# Cas_1.net
KiCad netlist of a schematic drawn in Altium Designer
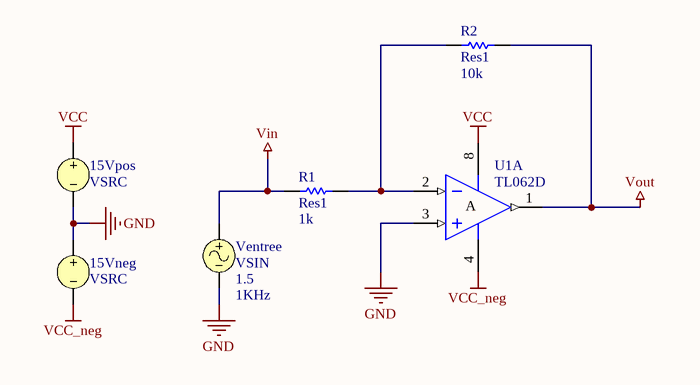
[diagram p0: Cas_1.SchDoc]

(export (version "E")
  (design (tool "Eeschema 10.0.6"))
  (components
    (comp (ref "15Vneg")
      (value "VSRC")
      (description "Voltage Source")
      (fields (field (name "PUBLISHER") "Altium Limited"))
      (libsource (lib "Simulation Generic Components") (part "VSRC"))
    )
    (comp (ref "15Vpos")
      (value "VSRC")
      (description "Voltage Source")
      (fields (field (name "PUBLISHER") "Altium Limited"))
      (libsource (lib "Simulation Generic Components") (part "VSRC"))
    )
    (comp (ref "R1")
      (value "Res1")
      (footprint "AXIAL-0.3")
      (description "Resistor")
      (fields (field (name "ALTIUM_VALUE") "1k") (field (name "PUBLISHER") "Altium Limited"))
      (libsource (lib "Miscellaneous Devices") (part "Res1"))
    )
    (comp (ref "R2")
      (value "Res1")
      (footprint "AXIAL-0.3")
      (description "Resistor")
      (fields (field (name "ALTIUM_VALUE") "10k") (field (name "PUBLISHER") "Altium Limited"))
      (libsource (lib "Miscellaneous Devices") (part "Res1"))
    )
    (comp (ref "U1")
      (value "TL062D")
      (footprint "D008_L")
      (description "Low-Power JFET-Input Operational Amplifier")
      (fields (field (name "PUBLISHER") "Altium Limited"))
      (libsource (lib "TI Operational Amplifier") (part "TL062D"))
    )
    (comp (ref "Ventree")
      (value "VSIN")
      (description "Sinusoidal Voltage Source")
      (fields
        (field (name "AMPLITUDE") "1.5")
        (field (name "FREQUENCY") "1KHz")
        (field (name "PUBLISHER") "Altium Limited")
      )
      (libsource (lib "Simulation Sources") (part "VSIN"))
    )
  )
  (nets
    (net (code "1") (name "GND") (class "Default")
      (node (ref "15Vneg") (pin "1") (pinfunction "1_1") (pintype "passive"))
      (node (ref "15Vpos") (pin "2") (pinfunction "2_2") (pintype "passive"))
      (node (ref "U1") (pin "3") (pinfunction "IN+_3") (pintype "input"))
      (node (ref "Ventree") (pin "2") (pinfunction "2_2") (pintype "passive"))
    )
    (net (code "2") (name "Net-(U1A-IN-)") (class "Default")
      (node (ref "R1") (pin "2") (pinfunction "2_2") (pintype "passive"))
      (node (ref "R2") (pin "1") (pinfunction "1_1") (pintype "passive"))
      (node (ref "U1") (pin "2") (pinfunction "IN-_2") (pintype "input"))
    )
    (net (code "3") (name "VCC") (class "Default")
      (node (ref "15Vpos") (pin "1") (pinfunction "1_1") (pintype "passive"))
      (node (ref "U1") (pin "8") (pinfunction "V+_8") (pintype "power_in"))
    )
    (net (code "4") (name "VCC_neg") (class "Default")
      (node (ref "15Vneg") (pin "2") (pinfunction "2_2") (pintype "passive"))
      (node (ref "U1") (pin "4") (pinfunction "V-_4") (pintype "power_in"))
    )
    (net (code "5") (name "Vin") (class "Default")
      (node (ref "R1") (pin "1") (pinfunction "1_1") (pintype "passive"))
      (node (ref "Ventree") (pin "1") (pinfunction "1_1") (pintype "passive"))
    )
    (net (code "6") (name "Vout") (class "Default")
      (node (ref "R2") (pin "2") (pinfunction "2_2") (pintype "passive"))
      (node (ref "U1") (pin "1") (pinfunction "OUT_1") (pintype "output"))
    )
  )
)
